# GateDriveSchematic.net
KiCad netlist of a schematic drawn in Altium Designer
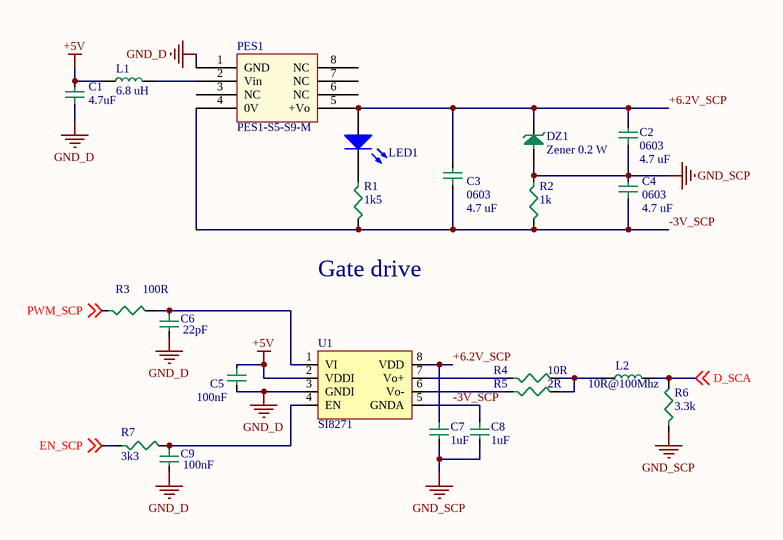
[diagram p0: GateDriveSchematic.SchDoc]

(export (version "E")
  (design (tool "Eeschema 10.0.6"))
  (components
    (comp (ref "C1")
      (value "4.7uF")
      (footprint "0603C")
      (description "Capacitor SMD 0603")
      (fields (field (name "Comment") "0603"))
      (libsource (lib "RLC_Integrated_Library") (part "Capacitor SMD 0603"))
    )
    (comp (ref "C2")
      (value "0603")
      (footprint "0603C")
      (description "Capacitor SMD 0603")
      (fields (field (name "ALTIUM_VALUE") "4.7 uF"))
      (libsource (lib "RLC_Integrated_Library") (part "Capacitor SMD 0603"))
    )
    (comp (ref "C3")
      (value "0603")
      (footprint "0603C")
      (description "Capacitor SMD 0603")
      (fields (field (name "ALTIUM_VALUE") "4.7 uF"))
      (libsource (lib "RLC_Integrated_Library") (part "Capacitor SMD 0603"))
    )
    (comp (ref "C4")
      (value "0603")
      (footprint "0603C")
      (description "Capacitor SMD 0603")
      (fields (field (name "ALTIUM_VALUE") "4.7 uF"))
      (libsource (lib "RLC_Integrated_Library") (part "Capacitor SMD 0603"))
    )
    (comp (ref "C5")
      (value "100nF")
      (footprint "0603C")
      (description "Capacitor SMD 0603")
      (fields (field (name "Comment") "0603"))
      (libsource (lib "RLC_Integrated_Library") (part "Capacitor SMD 0603"))
    )
    (comp (ref "C6")
      (value "22pF")
      (footprint "0603C")
      (description "Capacitor SMD 0603")
      (fields (field (name "Comment") "0603"))
      (libsource (lib "RLC_Integrated_Library") (part "Capacitor SMD 0603"))
    )
    (comp (ref "C7")
      (value "1uF")
      (footprint "0603C")
      (description "Capacitor SMD 0603")
      (fields (field (name "Comment") "0603"))
      (libsource (lib "RLC_Integrated_Library") (part "Capacitor SMD 0603"))
    )
    (comp (ref "C8")
      (value "1uF")
      (footprint "0603C")
      (description "Capacitor SMD 0603")
      (fields (field (name "Comment") "0603"))
      (libsource (lib "RLC_Integrated_Library") (part "Capacitor SMD 0603"))
    )
    (comp (ref "C9")
      (value "100nF")
      (footprint "0603C")
      (description "Capacitor SMD 0603")
      (fields (field (name "Comment") "0603"))
      (libsource (lib "RLC_Integrated_Library") (part "Capacitor SMD 0603"))
    )
    (comp (ref "DZ1")
      (value "Zener 0.2 W")
      (footprint "SODF323")
      (description "Zener Diodes ZEN REG 0.2W TR")
      (libsource (lib "Diodo_Transistor_Integrated_Library") (part "Diodo Zener SOD-323"))
    )
    (comp (ref "L1")
      (value "6.8 uH")
      (footprint "0805")
      (description "Indutor SMD 0805")
      (fields (field (name "Comment") "0805"))
      (libsource (lib "RLC_Integrated_Library") (part "Indutor SMD 0805"))
    )
    (comp (ref "L2")
      (value "10R@100Mhz")
      (footprint "0603")
      (description "Indutor SMD 0603")
      (fields (field (name "Comment") "0603"))
      (libsource (lib "RLC_Integrated_Library") (part "Indutor SMD 0603"))
    )
    (comp (ref "LED1")
      (value "LED 0603")
      (footprint "LED SMD 0603")
      (description "Typical INFRARED GaAs LED")
      (fields (field (name "PUBLISHER") "Altium Limited"))
      (libsource (lib "Diodo_Transistor_Integrated_Library") (part "LED 0603 SMD"))
    )
    (comp (ref "PES1")
      (value "PES1-S5-S9-M")
      (footprint "PES1")
      (description "Isolated DC/DC Converters 1W 5Vin 9Vout SMT 12-111mA Iso UnReg")
      (libsource (lib "Jose_lib") (part "PES1-M"))
    )
    (comp (ref "R1")
      (value "1k5")
      (footprint "0603")
      (description "Resistor SMD 0603 1/10 W")
      (fields (field (name "Comment") "0603"))
      (libsource (lib "RLC_Integrated_Library") (part "Resistor SMD 0603 1/10 W"))
    )
    (comp (ref "R2")
      (value "1k")
      (footprint "0603")
      (description "Resistor SMD 0603 1/10 W")
      (fields (field (name "Comment") "0603"))
      (libsource (lib "RLC_Integrated_Library") (part "Resistor SMD 0603 1/10 W"))
    )
    (comp (ref "R3")
      (value "100R")
      (footprint "0603")
      (description "Resistor SMD 0603 1/10 W")
      (fields (field (name "Comment") "0603"))
      (libsource (lib "RLC_Integrated_Library") (part "Resistor SMD 0603 1/10 W"))
    )
    (comp (ref "R4")
      (value "10R")
      (footprint "0603")
      (description "Resistor SMD 0603 1/10 W")
      (fields (field (name "Comment") "0603"))
      (libsource (lib "RLC_Integrated_Library") (part "Resistor SMD 0603 1/10 W"))
    )
    (comp (ref "R5")
      (value "2R")
      (footprint "0603")
      (description "Resistor SMD 0603 1/10 W")
      (fields (field (name "Comment") "0603"))
      (libsource (lib "RLC_Integrated_Library") (part "Resistor SMD 0603 1/10 W"))
    )
    (comp (ref "R6")
      (value "3.3k")
      (footprint "0603")
      (description "Resistor SMD 0603 1/10 W")
      (fields (field (name "Comment") "0603"))
      (libsource (lib "RLC_Integrated_Library") (part "Resistor SMD 0603 1/10 W"))
    )
    (comp (ref "R7")
      (value "3k3")
      (footprint "0603")
      (description "Resistor SMD 0603 1/10 W")
      (fields (field (name "Comment") "0603"))
      (libsource (lib "RLC_Integrated_Library") (part "Resistor SMD 0603 1/10 W"))
    )
    (comp (ref "U1")
      (value "SI8271")
      (footprint "SOIC 8")
      (description "Gate Drivers Hi CMTI 2.5 kV 3 V UVLO single isolated driver with deglitch")
      (libsource (lib "CI_Integrated_Library") (part "CI Driver GaN SI8271"))
    )
  )
  (nets
    (net (code "1") (name "+5V") (class "Default")
      (node (ref "C1") (pin "2") (pinfunction "2_2") (pintype "passive"))
      (node (ref "C5") (pin "1") (pinfunction "1_1") (pintype "passive"))
      (node (ref "L1") (pin "1") (pinfunction "1_1") (pintype "passive"))
      (node (ref "U1") (pin "2") (pinfunction "VDDI_2") (pintype "passive"))
    )
    (net (code "2") (name "/+6.2V_SCP") (class "Default")
      (node (ref "C2") (pin "2") (pinfunction "2_2") (pintype "passive"))
      (node (ref "C3") (pin "2") (pinfunction "2_2") (pintype "passive"))
      (node (ref "C7") (pin "1") (pinfunction "1_1") (pintype "passive"))
      (node (ref "DZ1") (pin "K") (pinfunction "K_K") (pintype "passive"))
      (node (ref "LED1") (pin "1") (pinfunction "A_1") (pintype "passive"))
      (node (ref "PES1") (pin "5") (pinfunction "+Vo_5") (pintype "passive"))
      (node (ref "U1") (pin "8") (pinfunction "VDD_8") (pintype "passive"))
    )
    (net (code "3") (name "/-3V_SCP") (class "Default")
      (node (ref "C3") (pin "1") (pinfunction "1_1") (pintype "passive"))
      (node (ref "C4") (pin "1") (pinfunction "1_1") (pintype "passive"))
      (node (ref "C8") (pin "1") (pinfunction "1_1") (pintype "passive"))
      (node (ref "PES1") (pin "4") (pinfunction "0V_4") (pintype "passive"))
      (node (ref "R1") (pin "2") (pinfunction "2_2") (pintype "passive"))
      (node (ref "R2") (pin "2") (pinfunction "2_2") (pintype "passive"))
      (node (ref "U1") (pin "5") (pinfunction "GNDA_5") (pintype "passive"))
    )
    (net (code "4") (name "D_SCA") (class "Default")
      (node (ref "L2") (pin "2") (pinfunction "2_2") (pintype "passive"))
      (node (ref "R6") (pin "2") (pinfunction "2_2") (pintype "passive"))
    )
    (net (code "5") (name "EN_SCP") (class "Default")
      (node (ref "R7") (pin "1") (pinfunction "1_1") (pintype "passive"))
    )
    (net (code "6") (name "GND_D") (class "Default")
      (node (ref "C1") (pin "1") (pinfunction "1_1") (pintype "passive"))
      (node (ref "C5") (pin "2") (pinfunction "2_2") (pintype "passive"))
      (node (ref "C6") (pin "2") (pinfunction "2_2") (pintype "passive"))
      (node (ref "C9") (pin "2") (pinfunction "2_2") (pintype "passive"))
      (node (ref "PES1") (pin "1") (pinfunction "GND_1") (pintype "passive"))
      (node (ref "U1") (pin "3") (pinfunction "GNDI_3") (pintype "passive"))
    )
    (net (code "7") (name "GND_SCP") (class "Default")
      (node (ref "C2") (pin "1") (pinfunction "1_1") (pintype "passive"))
      (node (ref "C4") (pin "2") (pinfunction "2_2") (pintype "passive"))
      (node (ref "C7") (pin "2") (pinfunction "2_2") (pintype "passive"))
      (node (ref "C8") (pin "2") (pinfunction "2_2") (pintype "passive"))
      (node (ref "DZ1") (pin "A") (pinfunction "A_A") (pintype "passive"))
      (node (ref "R2") (pin "1") (pinfunction "1_1") (pintype "passive"))
      (node (ref "R6") (pin "1") (pinfunction "1_1") (pintype "passive"))
    )
    (net (code "8") (name "Net-(L2-Pad1)") (class "Default")
      (node (ref "L2") (pin "1") (pinfunction "1_1") (pintype "passive"))
      (node (ref "R4") (pin "2") (pinfunction "2_2") (pintype "passive"))
      (node (ref "R5") (pin "2") (pinfunction "2_2") (pintype "passive"))
    )
    (net (code "9") (name "Net-(LED1-K)") (class "Default")
      (node (ref "LED1") (pin "2") (pinfunction "K_2") (pintype "passive"))
      (node (ref "R1") (pin "1") (pinfunction "1_1") (pintype "passive"))
    )
    (net (code "10") (name "Net-(PES1-Vin)") (class "Default")
      (node (ref "L1") (pin "2") (pinfunction "2_2") (pintype "passive"))
      (node (ref "PES1") (pin "2") (pinfunction "Vin_2") (pintype "passive"))
    )
    (net (code "11") (name "Net-(U1-EN)") (class "Default")
      (node (ref "C9") (pin "1") (pinfunction "1_1") (pintype "passive"))
      (node (ref "R7") (pin "2") (pinfunction "2_2") (pintype "passive"))
      (node (ref "U1") (pin "4") (pinfunction "EN_4") (pintype "passive"))
    )
    (net (code "12") (name "Net-(U1-VI)") (class "Default")
      (node (ref "C6") (pin "1") (pinfunction "1_1") (pintype "passive"))
      (node (ref "R3") (pin "2") (pinfunction "2_2") (pintype "passive"))
      (node (ref "U1") (pin "1") (pinfunction "VI_1") (pintype "passive"))
    )
    (net (code "13") (name "Net-(U1-Vo+)") (class "Default")
      (node (ref "R4") (pin "1") (pinfunction "1_1") (pintype "passive"))
      (node (ref "U1") (pin "7") (pinfunction "Vo+_7") (pintype "passive"))
    )
    (net (code "14") (name "Net-(U1-Vo-)") (class "Default")
      (node (ref "R5") (pin "1") (pinfunction "1_1") (pintype "passive"))
      (node (ref "U1") (pin "6") (pinfunction "Vo-_6") (pintype "passive"))
    )
    (net (code "15") (name "PWM_SCP") (class "Default")
      (node (ref "R3") (pin "1") (pinfunction "1_1") (pintype "passive"))
    )
    (net (code "16") (name "unconnected-(PES1-NC-Pad3)") (class "Default")
      (node (ref "PES1") (pin "3") (pinfunction "NC_3") (pintype "passive"))
    )
    (net (code "17") (name "unconnected-(PES1-NC-Pad6)") (class "Default")
      (node (ref "PES1") (pin "6") (pinfunction "NC_6") (pintype "passive"))
    )
    (net (code "18") (name "unconnected-(PES1-NC-Pad7)") (class "Default")
      (node (ref "PES1") (pin "7") (pinfunction "NC_7") (pintype "passive"))
    )
    (net (code "19") (name "unconnected-(PES1-NC-Pad8)") (class "Default")
      (node (ref "PES1") (pin "8") (pinfunction "NC_8") (pintype "passive"))
    )
  )
)
